# Door-outer.net
KiCad netlist of a schematic drawn in EAGLE
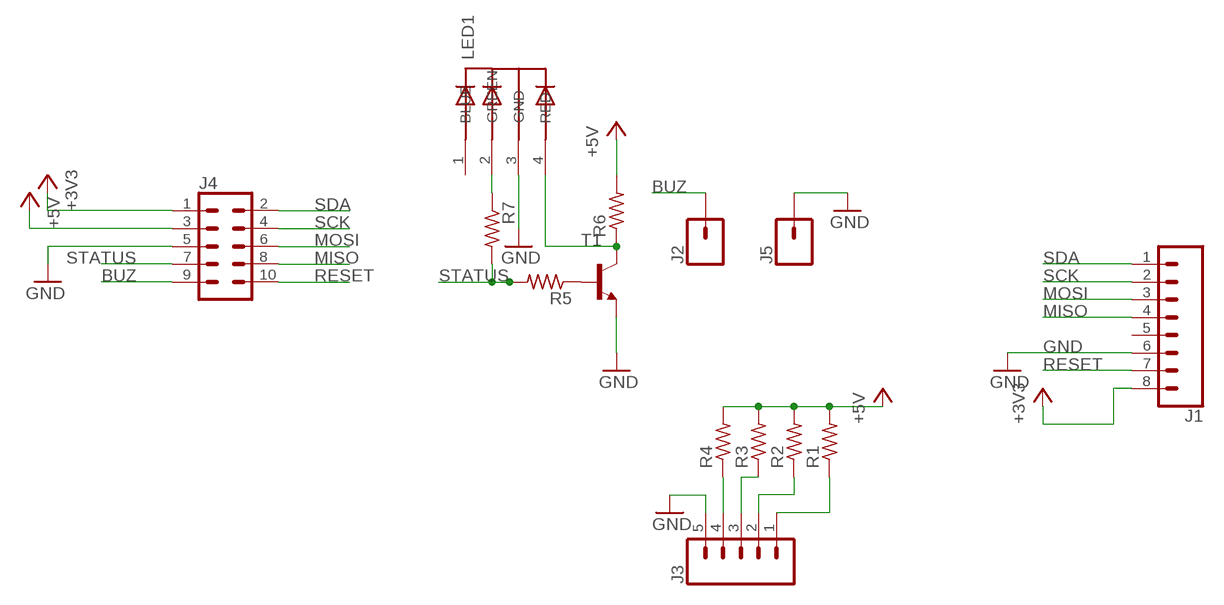
[diagram p0: schematic, sheet 1]

(export (version "E")
  (design (tool "Eeschema 10.0.6"))
  (components
    (comp (ref "J1")
      (value "CONN_08\"")
      (footprint "eagle-import:1X08")
      (libsource (lib "eagle-import") (part "CONN_08{dblquote}"))
    )
    (comp (ref "J2")
      (value "CONN_01PTH_NO_SILK_YES_STOP")
      (footprint "eagle-import:1X01_NO_SILK")
      (libsource (lib "eagle-import") (part "CONN_01PTH_NO_SILK_YES_STOP"))
    )
    (comp (ref "J3")
      (value "CONN_05")
      (footprint "eagle-import:1X05")
      (libsource (lib "eagle-import") (part "CONN_05"))
    )
    (comp (ref "J4")
      (value "CONN_05X2PTH")
      (footprint "eagle-import:2X5")
      (libsource (lib "eagle-import") (part "CONN_05X2PTH"))
    )
    (comp (ref "J5")
      (value "CONN_01PTH_NO_SILK_YES_STOP")
      (footprint "eagle-import:1X01_NO_SILK")
      (libsource (lib "eagle-import") (part "CONN_01PTH_NO_SILK_YES_STOP"))
    )
    (comp (ref "LED1")
      (value "5MMRGBLED")
      (footprint "eagle-import:LED5MMRGB")
      (libsource (lib "eagle-import") (part "5MMRGBLED"))
    )
    (comp (ref "R1")
      (value "R-US_R1206")
      (footprint "eagle-import:R1206")
      (libsource (lib "eagle-import") (part "R-US_R1206"))
    )
    (comp (ref "R2")
      (value "R-US_R1206")
      (footprint "eagle-import:R1206")
      (libsource (lib "eagle-import") (part "R-US_R1206"))
    )
    (comp (ref "R3")
      (value "R-US_R1206")
      (footprint "eagle-import:R1206")
      (libsource (lib "eagle-import") (part "R-US_R1206"))
    )
    (comp (ref "R4")
      (value "R-US_R1206")
      (footprint "eagle-import:R1206")
      (libsource (lib "eagle-import") (part "R-US_R1206"))
    )
    (comp (ref "R5")
      (value "R-US_R1206")
      (footprint "eagle-import:R1206")
      (libsource (lib "eagle-import") (part "R-US_R1206"))
    )
    (comp (ref "R6")
      (value "R-US_R1206")
      (footprint "eagle-import:R1206")
      (libsource (lib "eagle-import") (part "R-US_R1206"))
    )
    (comp (ref "R7")
      (value "R-US_R1206")
      (footprint "eagle-import:R1206")
      (libsource (lib "eagle-import") (part "R-US_R1206"))
    )
    (comp (ref "T1")
      (value "MPS2222A-NPN-TO92-CBE")
      (footprint "eagle-import:TO92-CBE")
      (libsource (lib "eagle-import") (part "-NPN-TO92-CBEMPS2222A"))
    )
  )
  (nets
    (net (code "1") (name "+3V3") (class "Default")
      (node (ref "J1") (pin "8") (pinfunction "8_8") (pintype "passive"))
      (node (ref "J4") (pin "1") (pinfunction "1_1") (pintype "passive"))
    )
    (net (code "2") (name "+5V") (class "Default")
      (node (ref "J4") (pin "3") (pinfunction "3_3") (pintype "passive"))
      (node (ref "R1") (pin "2") (pinfunction "2_2") (pintype "passive"))
      (node (ref "R2") (pin "2") (pinfunction "2_2") (pintype "passive"))
      (node (ref "R3") (pin "2") (pinfunction "2_2") (pintype "passive"))
      (node (ref "R4") (pin "2") (pinfunction "2_2") (pintype "passive"))
      (node (ref "R6") (pin "2") (pinfunction "2_2") (pintype "passive"))
    )
    (net (code "3") (name "/BUZ") (class "Default")
      (node (ref "J2") (pin "1") (pinfunction "1_1") (pintype "passive"))
      (node (ref "J4") (pin "9") (pinfunction "9_9") (pintype "passive"))
    )
    (net (code "4") (name "/MISO") (class "Default")
      (node (ref "J1") (pin "4") (pinfunction "4_4") (pintype "passive"))
      (node (ref "J4") (pin "8") (pinfunction "8_8") (pintype "passive"))
    )
    (net (code "5") (name "/MOSI") (class "Default")
      (node (ref "J1") (pin "3") (pinfunction "3_3") (pintype "passive"))
      (node (ref "J4") (pin "6") (pinfunction "6_6") (pintype "passive"))
    )
    (net (code "6") (name "/RESET") (class "Default")
      (node (ref "J1") (pin "7") (pinfunction "7_7") (pintype "passive"))
      (node (ref "J4") (pin "10") (pinfunction "10_10") (pintype "passive"))
    )
    (net (code "7") (name "/SCK") (class "Default")
      (node (ref "J1") (pin "2") (pinfunction "2_2") (pintype "passive"))
      (node (ref "J4") (pin "4") (pinfunction "4_4") (pintype "passive"))
    )
    (net (code "8") (name "/SDA") (class "Default")
      (node (ref "J1") (pin "1") (pinfunction "1_1") (pintype "passive"))
      (node (ref "J4") (pin "2") (pinfunction "2_2") (pintype "passive"))
    )
    (net (code "9") (name "/STATUS") (class "Default")
      (node (ref "J4") (pin "7") (pinfunction "7_7") (pintype "passive"))
      (node (ref "R5") (pin "2") (pinfunction "2_2") (pintype "passive"))
      (node (ref "R7") (pin "2") (pinfunction "2_2") (pintype "passive"))
    )
    (net (code "10") (name "GND") (class "Default")
      (node (ref "J1") (pin "6") (pinfunction "6_6") (pintype "passive"))
      (node (ref "J3") (pin "5") (pinfunction "5_5") (pintype "passive"))
      (node (ref "J4") (pin "5") (pinfunction "5_5") (pintype "passive"))
      (node (ref "J5") (pin "1") (pinfunction "1_1") (pintype "passive"))
      (node (ref "LED1") (pin "3") (pinfunction "GND_3") (pintype "bidirectional"))
      (node (ref "T1") (pin "E") (pinfunction "E_E") (pintype "passive"))
    )
    (net (code "11") (name "Net-(J3-Pad1)") (class "Default")
      (node (ref "J3") (pin "1") (pinfunction "1_1") (pintype "passive"))
      (node (ref "R1") (pin "1") (pinfunction "1_1") (pintype "passive"))
    )
    (net (code "12") (name "Net-(J3-Pad2)") (class "Default")
      (node (ref "J3") (pin "2") (pinfunction "2_2") (pintype "passive"))
      (node (ref "R2") (pin "1") (pinfunction "1_1") (pintype "passive"))
    )
    (net (code "13") (name "Net-(J3-Pad3)") (class "Default")
      (node (ref "J3") (pin "3") (pinfunction "3_3") (pintype "passive"))
      (node (ref "R3") (pin "1") (pinfunction "1_1") (pintype "passive"))
    )
    (net (code "14") (name "Net-(J3-Pad4)") (class "Default")
      (node (ref "J3") (pin "4") (pinfunction "4_4") (pintype "passive"))
      (node (ref "R4") (pin "1") (pinfunction "1_1") (pintype "passive"))
    )
    (net (code "15") (name "Net-(LED1-GREEN)") (class "Default")
      (node (ref "LED1") (pin "2") (pinfunction "GREEN_2") (pintype "bidirectional"))
      (node (ref "R7") (pin "1") (pinfunction "1_1") (pintype "passive"))
    )
    (net (code "16") (name "Net-(LED1-RED)") (class "Default")
      (node (ref "LED1") (pin "4") (pinfunction "RED_4") (pintype "bidirectional"))
      (node (ref "R6") (pin "1") (pinfunction "1_1") (pintype "passive"))
      (node (ref "T1") (pin "C") (pinfunction "C_C") (pintype "passive"))
    )
    (net (code "17") (name "Net-(R5-Pad1)") (class "Default")
      (node (ref "R5") (pin "1") (pinfunction "1_1") (pintype "passive"))
      (node (ref "T1") (pin "B") (pinfunction "B_B") (pintype "passive"))
    )
    (net (code "18") (name "unconnected-(J1-Pad5)") (class "Default")
      (node (ref "J1") (pin "5") (pinfunction "5_5") (pintype "passive"))
    )
    (net (code "19") (name "unconnected-(LED1-BLUE-Pad1)") (class "Default")
      (node (ref "LED1") (pin "1") (pinfunction "BLUE_1") (pintype "bidirectional"))
    )
  )
)
